# mfos_vco_shapers.net
KiCad netlist of a schematic drawn in EAGLE
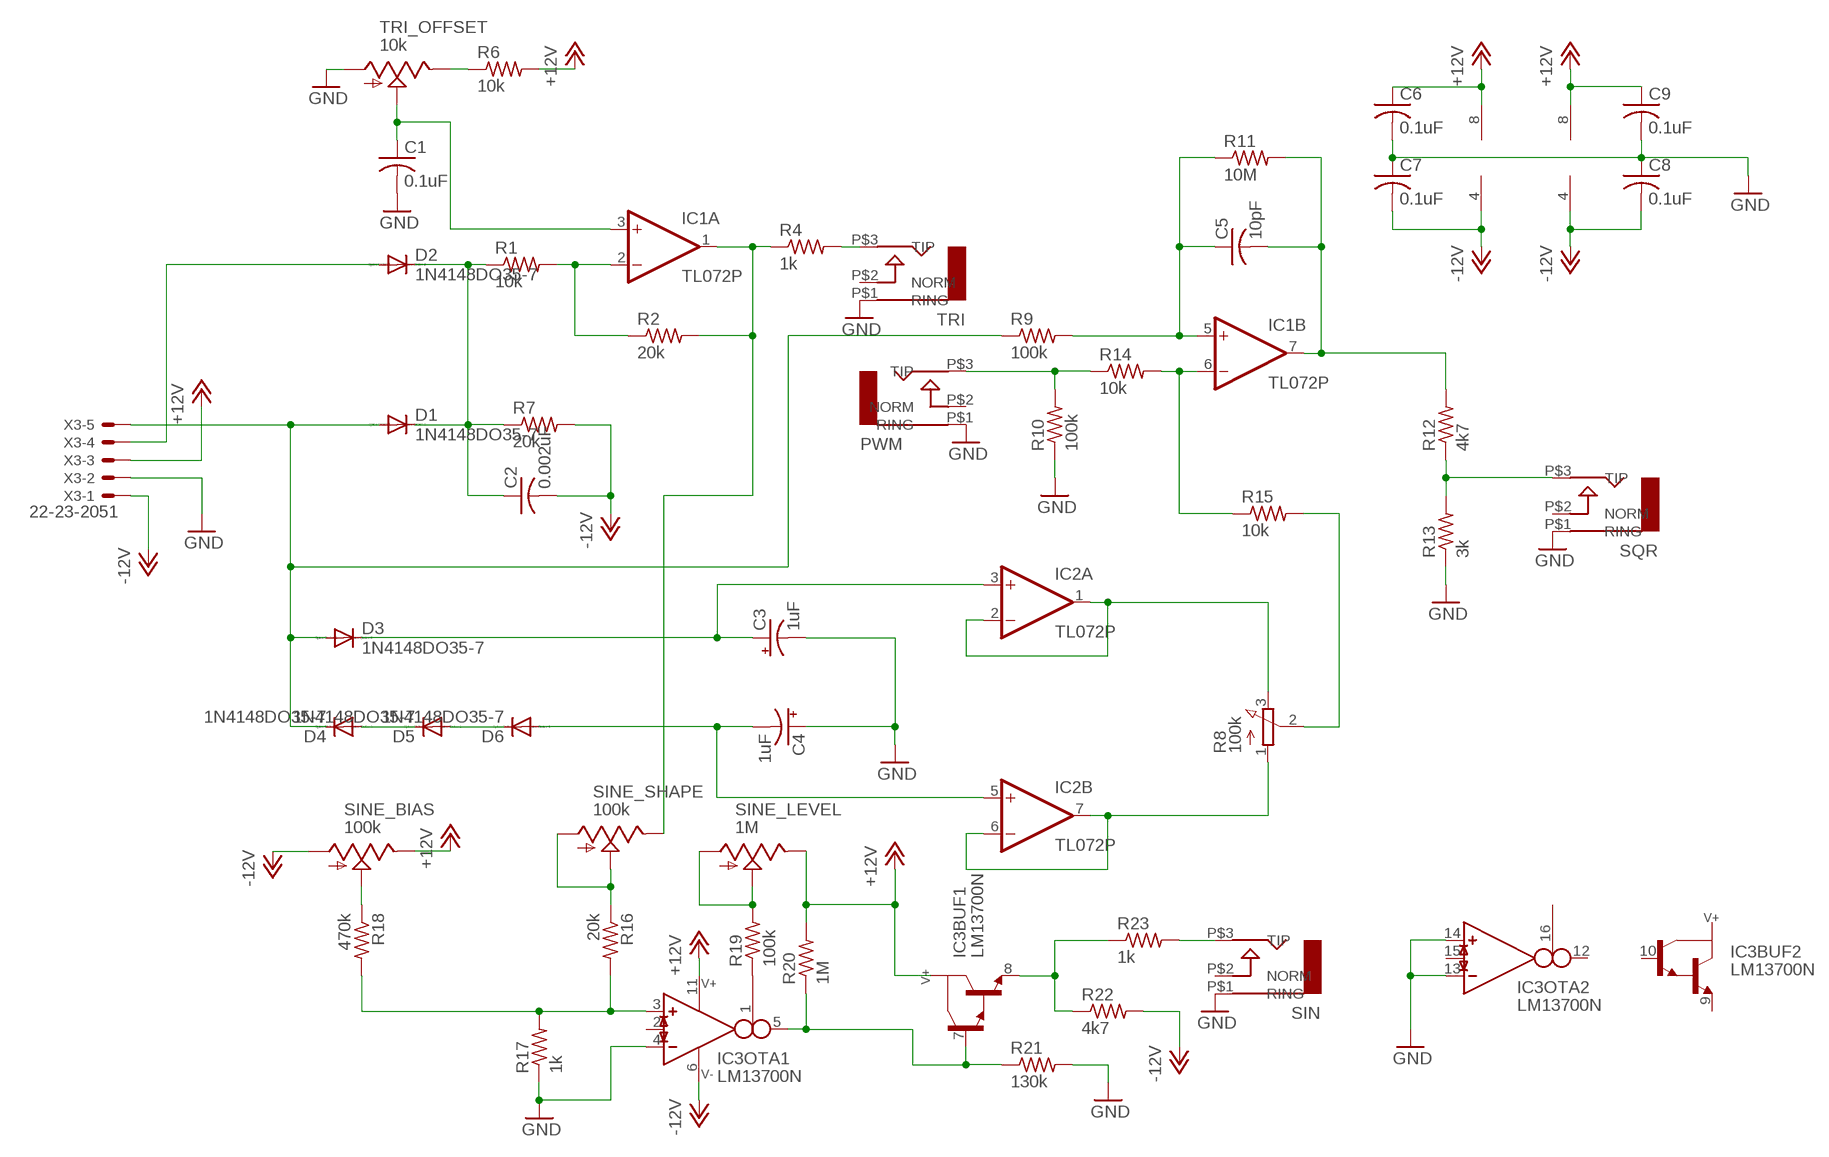
[diagram p0: schematic, sheet 1]

(export (version "E")
  (design (tool "Eeschema 10.0.6"))
  (components
    (comp (ref "C1")
      (value "0.1uF")
      (footprint "eagle-import:C050-030X075")
      (libsource (lib "eagle-import") (part "C-US050-030X075"))
    )
    (comp (ref "C2")
      (value "0.002uF")
      (footprint "eagle-import:C050-030X075")
      (libsource (lib "eagle-import") (part "C-US050-030X075"))
    )
    (comp (ref "C3")
      (value "1uF")
      (footprint "eagle-import:B45181B")
      (libsource (lib "eagle-import") (part "CPOL-USB45181B"))
    )
    (comp (ref "C4")
      (value "1uF")
      (footprint "eagle-import:B45181B")
      (libsource (lib "eagle-import") (part "CPOL-USB45181B"))
    )
    (comp (ref "C5")
      (value "10pF")
      (footprint "eagle-import:C050-024X044")
      (libsource (lib "eagle-import") (part "C-US050-024X044"))
    )
    (comp (ref "C6")
      (value "0.1uF")
      (footprint "eagle-import:C050-030X075")
      (libsource (lib "eagle-import") (part "C-US050-030X075"))
    )
    (comp (ref "C7")
      (value "0.1uF")
      (footprint "eagle-import:C050-030X075")
      (libsource (lib "eagle-import") (part "C-US050-030X075"))
    )
    (comp (ref "C8")
      (value "0.1uF")
      (footprint "eagle-import:C050-030X075")
      (libsource (lib "eagle-import") (part "C-US050-030X075"))
    )
    (comp (ref "C9")
      (value "0.1uF")
      (footprint "eagle-import:C050-030X075")
      (libsource (lib "eagle-import") (part "C-US050-030X075"))
    )
    (comp (ref "D1")
      (value "1N4148DO35-7")
      (footprint "eagle-import:DO35-7")
      (libsource (lib "eagle-import") (part "1N4148DO35-7"))
    )
    (comp (ref "D2")
      (value "1N4148DO35-7")
      (footprint "eagle-import:DO35-7")
      (libsource (lib "eagle-import") (part "1N4148DO35-7"))
    )
    (comp (ref "D3")
      (value "1N4148DO35-7")
      (footprint "eagle-import:DO35-7")
      (libsource (lib "eagle-import") (part "1N4148DO35-7"))
    )
    (comp (ref "D4")
      (value "1N4148DO35-7")
      (footprint "eagle-import:DO35-7")
      (libsource (lib "eagle-import") (part "1N4148DO35-7"))
    )
    (comp (ref "D5")
      (value "1N4148DO35-7")
      (footprint "eagle-import:DO35-7")
      (libsource (lib "eagle-import") (part "1N4148DO35-7"))
    )
    (comp (ref "D6")
      (value "1N4148DO35-7")
      (footprint "eagle-import:DO35-7")
      (libsource (lib "eagle-import") (part "1N4148DO35-7"))
    )
    (comp (ref "IC1")
      (value "TL072P")
      (footprint "eagle-import:DIL08")
      (libsource (lib "eagle-import") (part "TL072P"))
    )
    (comp (ref "IC2")
      (value "TL072P")
      (footprint "eagle-import:DIL08")
      (libsource (lib "eagle-import") (part "TL072P"))
    )
    (comp (ref "IC3")
      (value "LM13700N")
      (footprint "eagle-import:DIL16")
      (libsource (lib "eagle-import") (part "LM13700N"))
    )
    (comp (ref "PWM")
      (value "AUDIO-JACK")
      (footprint "eagle-import:ERTHENVAR-JACK-90DEG")
      (libsource (lib "eagle-import") (part "AUDIO-JACK"))
    )
    (comp (ref "R1")
      (value "10k")
      (footprint "eagle-import:0207_7")
      (libsource (lib "eagle-import") (part "R-US_0207/7"))
    )
    (comp (ref "R2")
      (value "20k")
      (footprint "eagle-import:0207_7")
      (libsource (lib "eagle-import") (part "R-US_0207/7"))
    )
    (comp (ref "R4")
      (value "1k")
      (footprint "eagle-import:0207_7")
      (libsource (lib "eagle-import") (part "R-US_0207/7"))
    )
    (comp (ref "R6")
      (value "10k")
      (footprint "eagle-import:0207_7")
      (libsource (lib "eagle-import") (part "R-US_0207/7"))
    )
    (comp (ref "R7")
      (value "20k")
      (footprint "eagle-import:0207_7")
      (libsource (lib "eagle-import") (part "R-US_0207/7"))
    )
    (comp (ref "R8")
      (value "100k")
      (footprint "eagle-import:3RP_1610N")
      (libsource (lib "eagle-import") (part "3RP/1610N"))
    )
    (comp (ref "R9")
      (value "100k")
      (footprint "eagle-import:0207_7")
      (libsource (lib "eagle-import") (part "R-US_0207/7"))
    )
    (comp (ref "R10")
      (value "100k")
      (footprint "eagle-import:0207_7")
      (libsource (lib "eagle-import") (part "R-US_0207/7"))
    )
    (comp (ref "R11")
      (value "10M")
      (footprint "eagle-import:0207_7")
      (libsource (lib "eagle-import") (part "R-US_0207/7"))
    )
    (comp (ref "R12")
      (value "4k7")
      (footprint "eagle-import:0207_7")
      (libsource (lib "eagle-import") (part "R-US_0207/7"))
    )
    (comp (ref "R13")
      (value "3k")
      (footprint "eagle-import:0207_7")
      (libsource (lib "eagle-import") (part "R-US_0207/7"))
    )
    (comp (ref "R14")
      (value "10k")
      (footprint "eagle-import:0207_7")
      (libsource (lib "eagle-import") (part "R-US_0207/7"))
    )
    (comp (ref "R15")
      (value "10k")
      (footprint "eagle-import:0207_7")
      (libsource (lib "eagle-import") (part "R-US_0207/7"))
    )
    (comp (ref "R16")
      (value "20k")
      (footprint "eagle-import:0207_7")
      (libsource (lib "eagle-import") (part "R-US_0207/7"))
    )
    (comp (ref "R17")
      (value "1k")
      (footprint "eagle-import:0207_7")
      (libsource (lib "eagle-import") (part "R-US_0207/7"))
    )
    (comp (ref "R18")
      (value "470k")
      (footprint "eagle-import:0207_7")
      (libsource (lib "eagle-import") (part "R-US_0207/7"))
    )
    (comp (ref "R19")
      (value "100k")
      (footprint "eagle-import:0207_7")
      (libsource (lib "eagle-import") (part "R-US_0207/7"))
    )
    (comp (ref "R20")
      (value "1M")
      (footprint "eagle-import:0207_7")
      (libsource (lib "eagle-import") (part "R-US_0207/7"))
    )
    (comp (ref "R21")
      (value "130k")
      (footprint "eagle-import:0207_7")
      (libsource (lib "eagle-import") (part "R-US_0207/7"))
    )
    (comp (ref "R22")
      (value "4k7")
      (footprint "eagle-import:0207_7")
      (libsource (lib "eagle-import") (part "R-US_0207/7"))
    )
    (comp (ref "R23")
      (value "1k")
      (footprint "eagle-import:0207_7")
      (libsource (lib "eagle-import") (part "R-US_0207/7"))
    )
    (comp (ref "SIN")
      (value "AUDIO-JACK")
      (footprint "eagle-import:ERTHENVAR-JACK-90DEG")
      (libsource (lib "eagle-import") (part "AUDIO-JACK"))
    )
    (comp (ref "SINE_BIAS")
      (value "100k")
      (footprint "eagle-import:B64Y")
      (libsource (lib "eagle-import") (part "TRIM_US-B64Y"))
    )
    (comp (ref "SINE_LEVEL")
      (value "1M")
      (footprint "eagle-import:B64Y")
      (libsource (lib "eagle-import") (part "TRIM_US-B64Y"))
    )
    (comp (ref "SINE_SHAPE")
      (value "100k")
      (footprint "eagle-import:B64Y")
      (libsource (lib "eagle-import") (part "TRIM_US-B64Y"))
    )
    (comp (ref "SQR")
      (value "AUDIO-JACK")
      (footprint "eagle-import:ERTHENVAR-JACK-90DEG")
      (libsource (lib "eagle-import") (part "AUDIO-JACK"))
    )
    (comp (ref "TRI")
      (value "AUDIO-JACK")
      (footprint "eagle-import:ERTHENVAR-JACK-90DEG")
      (libsource (lib "eagle-import") (part "AUDIO-JACK"))
    )
    (comp (ref "TRI_OFFSET")
      (value "10k")
      (footprint "eagle-import:B64Y")
      (libsource (lib "eagle-import") (part "TRIM_US-B64Y"))
    )
    (comp (ref "X3")
      (value "22-23-2051")
      (footprint "eagle-import:22-23-2051")
      (fields (field (name "MF") "MOLEX"))
      (libsource (lib "eagle-import") (part "22-23-2051"))
    )
  )
  (nets
    (net (code "1") (name "+12V") (class "Default")
      (node (ref "C6") (pin "1") (pinfunction "1_1") (pintype "passive"))
      (node (ref "C9") (pin "1") (pinfunction "1_1") (pintype "passive"))
      (node (ref "IC1") (pin "8") (pinfunction "V+_8") (pintype "power_in"))
      (node (ref "IC2") (pin "8") (pinfunction "V+_8") (pintype "power_in"))
      (node (ref "IC3") (pin "11") (pinfunction "V+_11") (pintype "power_in"))
      (node (ref "R20") (pin "2") (pinfunction "2_2") (pintype "passive"))
      (node (ref "R6") (pin "2") (pinfunction "2_2") (pintype "passive"))
      (node (ref "SINE_BIAS") (pin "E") (pinfunction "E_E") (pintype "passive"))
      (node (ref "SINE_LEVEL") (pin "E") (pinfunction "E_E") (pintype "passive"))
      (node (ref "X3") (pin "3") (pinfunction "S_3") (pintype "passive"))
    )
    (net (code "2") (name "-12V") (class "Default")
      (node (ref "C2") (pin "2") (pinfunction "2_2") (pintype "passive"))
      (node (ref "C7") (pin "2") (pinfunction "2_2") (pintype "passive"))
      (node (ref "C8") (pin "2") (pinfunction "2_2") (pintype "passive"))
      (node (ref "IC1") (pin "4") (pinfunction "V-_4") (pintype "power_in"))
      (node (ref "IC2") (pin "4") (pinfunction "V-_4") (pintype "power_in"))
      (node (ref "IC3") (pin "6") (pinfunction "V-_6") (pintype "power_in"))
      (node (ref "R22") (pin "2") (pinfunction "2_2") (pintype "passive"))
      (node (ref "R7") (pin "2") (pinfunction "2_2") (pintype "passive"))
      (node (ref "SINE_BIAS") (pin "A") (pinfunction "A_A") (pintype "passive"))
      (node (ref "X3") (pin "1") (pinfunction "S_1") (pintype "passive"))
    )
    (net (code "3") (name "GND") (class "Default")
      (node (ref "C1") (pin "2") (pinfunction "2_2") (pintype "passive"))
      (node (ref "C3") (pin "-") (pinfunction "-_-") (pintype "passive"))
      (node (ref "C4") (pin "+") (pinfunction "+_+") (pintype "passive"))
      (node (ref "C6") (pin "2") (pinfunction "2_2") (pintype "passive"))
      (node (ref "C7") (pin "1") (pinfunction "1_1") (pintype "passive"))
      (node (ref "C8") (pin "1") (pinfunction "1_1") (pintype "passive"))
      (node (ref "C9") (pin "2") (pinfunction "2_2") (pintype "passive"))
      (node (ref "IC3") (pin "13") (pinfunction "IN_N_13") (pintype "input"))
      (node (ref "IC3") (pin "14") (pinfunction "IN_P_14") (pintype "input"))
      (node (ref "IC3") (pin "4") (pinfunction "IN_N_4") (pintype "input"))
      (node (ref "PWM") (pin "P$1") (pinfunction "RING_P$1") (pintype "bidirectional"))
      (node (ref "R10") (pin "1") (pinfunction "1_1") (pintype "passive"))
      (node (ref "R13") (pin "1") (pinfunction "1_1") (pintype "passive"))
      (node (ref "R17") (pin "1") (pinfunction "1_1") (pintype "passive"))
      (node (ref "R21") (pin "2") (pinfunction "2_2") (pintype "passive"))
      (node (ref "SIN") (pin "P$1") (pinfunction "RING_P$1") (pintype "bidirectional"))
      (node (ref "SQR") (pin "P$1") (pinfunction "RING_P$1") (pintype "bidirectional"))
      (node (ref "TRI") (pin "P$1") (pinfunction "RING_P$1") (pintype "bidirectional"))
      (node (ref "TRI_OFFSET") (pin "A") (pinfunction "A_A") (pintype "passive"))
      (node (ref "X3") (pin "2") (pinfunction "S_2") (pintype "passive"))
    )
    (net (code "4") (name "Net-(C2-Pad1)") (class "Default")
      (node (ref "C2") (pin "1") (pinfunction "1_1") (pintype "passive"))
      (node (ref "D1") (pin "C") (pinfunction "C_C") (pintype "passive"))
      (node (ref "D2") (pin "C") (pinfunction "C_C") (pintype "passive"))
      (node (ref "R1") (pin "1") (pinfunction "1_1") (pintype "passive"))
      (node (ref "R7") (pin "1") (pinfunction "1_1") (pintype "passive"))
    )
    (net (code "5") (name "Net-(D4-PadA)") (class "Default")
      (node (ref "D4") (pin "A") (pinfunction "A_A") (pintype "passive"))
      (node (ref "D5") (pin "C") (pinfunction "C_C") (pintype "passive"))
    )
    (net (code "6") (name "Net-(D5-PadA)") (class "Default")
      (node (ref "D5") (pin "A") (pinfunction "A_A") (pintype "passive"))
      (node (ref "D6") (pin "C") (pinfunction "C_C") (pintype "passive"))
    )
    (net (code "7") (name "Net-(IC1A-+IN)") (class "Default")
      (node (ref "C1") (pin "1") (pinfunction "1_1") (pintype "passive"))
      (node (ref "IC1") (pin "3") (pinfunction "+IN_3") (pintype "input"))
      (node (ref "TRI_OFFSET") (pin "S") (pinfunction "S_S") (pintype "passive"))
    )
    (net (code "8") (name "Net-(IC1A--IN)") (class "Default")
      (node (ref "IC1") (pin "2") (pinfunction "-IN_2") (pintype "input"))
      (node (ref "R1") (pin "2") (pinfunction "2_2") (pintype "passive"))
      (node (ref "R2") (pin "1") (pinfunction "1_1") (pintype "passive"))
    )
    (net (code "9") (name "Net-(IC1A-OUT)") (class "Default")
      (node (ref "IC1") (pin "1") (pinfunction "OUT_1") (pintype "output"))
      (node (ref "R2") (pin "2") (pinfunction "2_2") (pintype "passive"))
      (node (ref "R4") (pin "1") (pinfunction "1_1") (pintype "passive"))
      (node (ref "SINE_SHAPE") (pin "E") (pinfunction "E_E") (pintype "passive"))
    )
    (net (code "10") (name "Net-(IC1B-+IN)") (class "Default")
      (node (ref "C5") (pin "1") (pinfunction "1_1") (pintype "passive"))
      (node (ref "IC1") (pin "5") (pinfunction "+IN_5") (pintype "input"))
      (node (ref "R11") (pin "1") (pinfunction "1_1") (pintype "passive"))
      (node (ref "R9") (pin "2") (pinfunction "2_2") (pintype "passive"))
    )
    (net (code "11") (name "Net-(IC1B--IN)") (class "Default")
      (node (ref "IC1") (pin "6") (pinfunction "-IN_6") (pintype "input"))
      (node (ref "R14") (pin "2") (pinfunction "2_2") (pintype "passive"))
      (node (ref "R15") (pin "1") (pinfunction "1_1") (pintype "passive"))
    )
    (net (code "12") (name "Net-(IC1B-OUT)") (class "Default")
      (node (ref "C5") (pin "2") (pinfunction "2_2") (pintype "passive"))
      (node (ref "IC1") (pin "7") (pinfunction "OUT_7") (pintype "output"))
      (node (ref "R11") (pin "2") (pinfunction "2_2") (pintype "passive"))
      (node (ref "R12") (pin "2") (pinfunction "2_2") (pintype "passive"))
    )
    (net (code "13") (name "Net-(IC2A-+IN)") (class "Default")
      (node (ref "C3") (pin "+") (pinfunction "+_+") (pintype "passive"))
      (node (ref "D3") (pin "C") (pinfunction "C_C") (pintype "passive"))
      (node (ref "IC2") (pin "3") (pinfunction "+IN_3") (pintype "input"))
    )
    (net (code "14") (name "Net-(IC2A--IN)") (class "Default")
      (node (ref "IC2") (pin "1") (pinfunction "OUT_1") (pintype "output"))
      (node (ref "IC2") (pin "2") (pinfunction "-IN_2") (pintype "input"))
      (node (ref "R8") (pin "3") (pinfunction "E_3") (pintype "passive"))
    )
    (net (code "15") (name "Net-(IC2B-+IN)") (class "Default")
      (node (ref "C4") (pin "-") (pinfunction "-_-") (pintype "passive"))
      (node (ref "D6") (pin "A") (pinfunction "A_A") (pintype "passive"))
      (node (ref "IC2") (pin "5") (pinfunction "+IN_5") (pintype "input"))
    )
    (net (code "16") (name "Net-(IC2B--IN)") (class "Default")
      (node (ref "IC2") (pin "6") (pinfunction "-IN_6") (pintype "input"))
      (node (ref "IC2") (pin "7") (pinfunction "OUT_7") (pintype "output"))
      (node (ref "R8") (pin "1") (pinfunction "A_1") (pintype "passive"))
    )
    (net (code "17") (name "Net-(IC3A-B)") (class "Default")
      (node (ref "IC3") (pin "5") (pinfunction "OUT_5") (pintype "output"))
      (node (ref "IC3") (pin "7") (pinfunction "B_7") (pintype "passive"))
      (node (ref "R20") (pin "1") (pinfunction "1_1") (pintype "passive"))
      (node (ref "R21") (pin "1") (pinfunction "1_1") (pintype "passive"))
    )
    (net (code "18") (name "Net-(IC3A-E)") (class "Default")
      (node (ref "IC3") (pin "8") (pinfunction "E_8") (pintype "passive"))
      (node (ref "R22") (pin "1") (pinfunction "1_1") (pintype "passive"))
      (node (ref "R23") (pin "1") (pinfunction "1_1") (pintype "passive"))
    )
    (net (code "19") (name "Net-(IC3C-IN_P)") (class "Default")
      (node (ref "IC3") (pin "3") (pinfunction "IN_P_3") (pintype "input"))
      (node (ref "R16") (pin "2") (pinfunction "2_2") (pintype "passive"))
      (node (ref "R17") (pin "2") (pinfunction "2_2") (pintype "passive"))
      (node (ref "R18") (pin "2") (pinfunction "2_2") (pintype "passive"))
    )
    (net (code "20") (name "Net-(IC3C-I_BIAS)") (class "Default")
      (node (ref "IC3") (pin "1") (pinfunction "I_BIAS_1") (pintype "input"))
      (node (ref "R19") (pin "1") (pinfunction "1_1") (pintype "passive"))
    )
    (net (code "21") (name "Net-(PWM-TIP)") (class "Default")
      (node (ref "PWM") (pin "P$3") (pinfunction "TIP_P$3") (pintype "bidirectional"))
      (node (ref "R10") (pin "2") (pinfunction "2_2") (pintype "passive"))
      (node (ref "R14") (pin "1") (pinfunction "1_1") (pintype "passive"))
    )
    (net (code "22") (name "Net-(R6-Pad1)") (class "Default")
      (node (ref "R6") (pin "1") (pinfunction "1_1") (pintype "passive"))
      (node (ref "TRI_OFFSET") (pin "E") (pinfunction "E_E") (pintype "passive"))
    )
    (net (code "23") (name "Net-(R8-S)") (class "Default")
      (node (ref "R15") (pin "2") (pinfunction "2_2") (pintype "passive"))
      (node (ref "R8") (pin "2") (pinfunction "S_2") (pintype "passive"))
    )
    (net (code "24") (name "Net-(R16-Pad1)") (class "Default")
      (node (ref "R16") (pin "1") (pinfunction "1_1") (pintype "passive"))
      (node (ref "SINE_SHAPE") (pin "A") (pinfunction "A_A") (pintype "passive"))
      (node (ref "SINE_SHAPE") (pin "S") (pinfunction "S_S") (pintype "passive"))
    )
    (net (code "25") (name "Net-(R18-Pad1)") (class "Default")
      (node (ref "R18") (pin "1") (pinfunction "1_1") (pintype "passive"))
      (node (ref "SINE_BIAS") (pin "S") (pinfunction "S_S") (pintype "passive"))
    )
    (net (code "26") (name "Net-(R19-Pad2)") (class "Default")
      (node (ref "R19") (pin "2") (pinfunction "2_2") (pintype "passive"))
      (node (ref "SINE_LEVEL") (pin "A") (pinfunction "A_A") (pintype "passive"))
      (node (ref "SINE_LEVEL") (pin "S") (pinfunction "S_S") (pintype "passive"))
    )
    (net (code "27") (name "Net-(SIN-TIP)") (class "Default")
      (node (ref "R23") (pin "2") (pinfunction "2_2") (pintype "passive"))
      (node (ref "SIN") (pin "P$3") (pinfunction "TIP_P$3") (pintype "bidirectional"))
    )
    (net (code "28") (name "Net-(SQR-TIP)") (class "Default")
      (node (ref "R12") (pin "1") (pinfunction "1_1") (pintype "passive"))
      (node (ref "R13") (pin "2") (pinfunction "2_2") (pintype "passive"))
      (node (ref "SQR") (pin "P$3") (pinfunction "TIP_P$3") (pintype "bidirectional"))
    )
    (net (code "29") (name "Net-(TRI-TIP)") (class "Default")
      (node (ref "R4") (pin "2") (pinfunction "2_2") (pintype "passive"))
      (node (ref "TRI") (pin "P$3") (pinfunction "TIP_P$3") (pintype "bidirectional"))
    )
    (net (code "30") (name "Net-(X3D-S)") (class "Default")
      (node (ref "D2") (pin "A") (pinfunction "A_A") (pintype "passive"))
      (node (ref "X3") (pin "4") (pinfunction "S_4") (pintype "passive"))
    )
    (net (code "31") (name "Net-(X3E-S)") (class "Default")
      (node (ref "D1") (pin "A") (pinfunction "A_A") (pintype "passive"))
      (node (ref "D3") (pin "A") (pinfunction "A_A") (pintype "passive"))
      (node (ref "D4") (pin "C") (pinfunction "C_C") (pintype "passive"))
      (node (ref "R9") (pin "1") (pinfunction "1_1") (pintype "passive"))
      (node (ref "X3") (pin "5") (pinfunction "S_5") (pintype "passive"))
    )
    (net (code "32") (name "unconnected-(IC3B-B-Pad10)") (class "Default")
      (node (ref "IC3") (pin "10") (pinfunction "B_10") (pintype "passive"))
    )
    (net (code "33") (name "unconnected-(IC3B-E-Pad9)") (class "Default")
      (node (ref "IC3") (pin "9") (pinfunction "E_9") (pintype "passive"))
    )
    (net (code "34") (name "unconnected-(IC3C-I_DIODE-Pad2)") (class "Default")
      (node (ref "IC3") (pin "2") (pinfunction "I_DIODE_2") (pintype "input"))
    )
    (net (code "35") (name "unconnected-(IC3D-I_BIAS-Pad16)") (class "Default")
      (node (ref "IC3") (pin "16") (pinfunction "I_BIAS_16") (pintype "input"))
    )
    (net (code "36") (name "unconnected-(IC3D-I_DIODE-Pad15)") (class "Default")
      (node (ref "IC3") (pin "15") (pinfunction "I_DIODE_15") (pintype "input"))
    )
    (net (code "37") (name "unconnected-(IC3D-OUT-Pad12)") (class "Default")
      (node (ref "IC3") (pin "12") (pinfunction "OUT_12") (pintype "output"))
    )
    (net (code "38") (name "unconnected-(PWM-NORM-PadP$2)") (class "Default")
      (node (ref "PWM") (pin "P$2") (pinfunction "NORM_P$2") (pintype "bidirectional"))
    )
    (net (code "39") (name "unconnected-(SIN-NORM-PadP$2)") (class "Default")
      (node (ref "SIN") (pin "P$2") (pinfunction "NORM_P$2") (pintype "bidirectional"))
    )
    (net (code "40") (name "unconnected-(SQR-NORM-PadP$2)") (class "Default")
      (node (ref "SQR") (pin "P$2") (pinfunction "NORM_P$2") (pintype "bidirectional"))
    )
    (net (code "41") (name "unconnected-(TRI-NORM-PadP$2)") (class "Default")
      (node (ref "TRI") (pin "P$2") (pinfunction "NORM_P$2") (pintype "bidirectional"))
    )
  )
)
